# h2oiq_v4.net
KiCad netlist of a schematic drawn in EAGLE
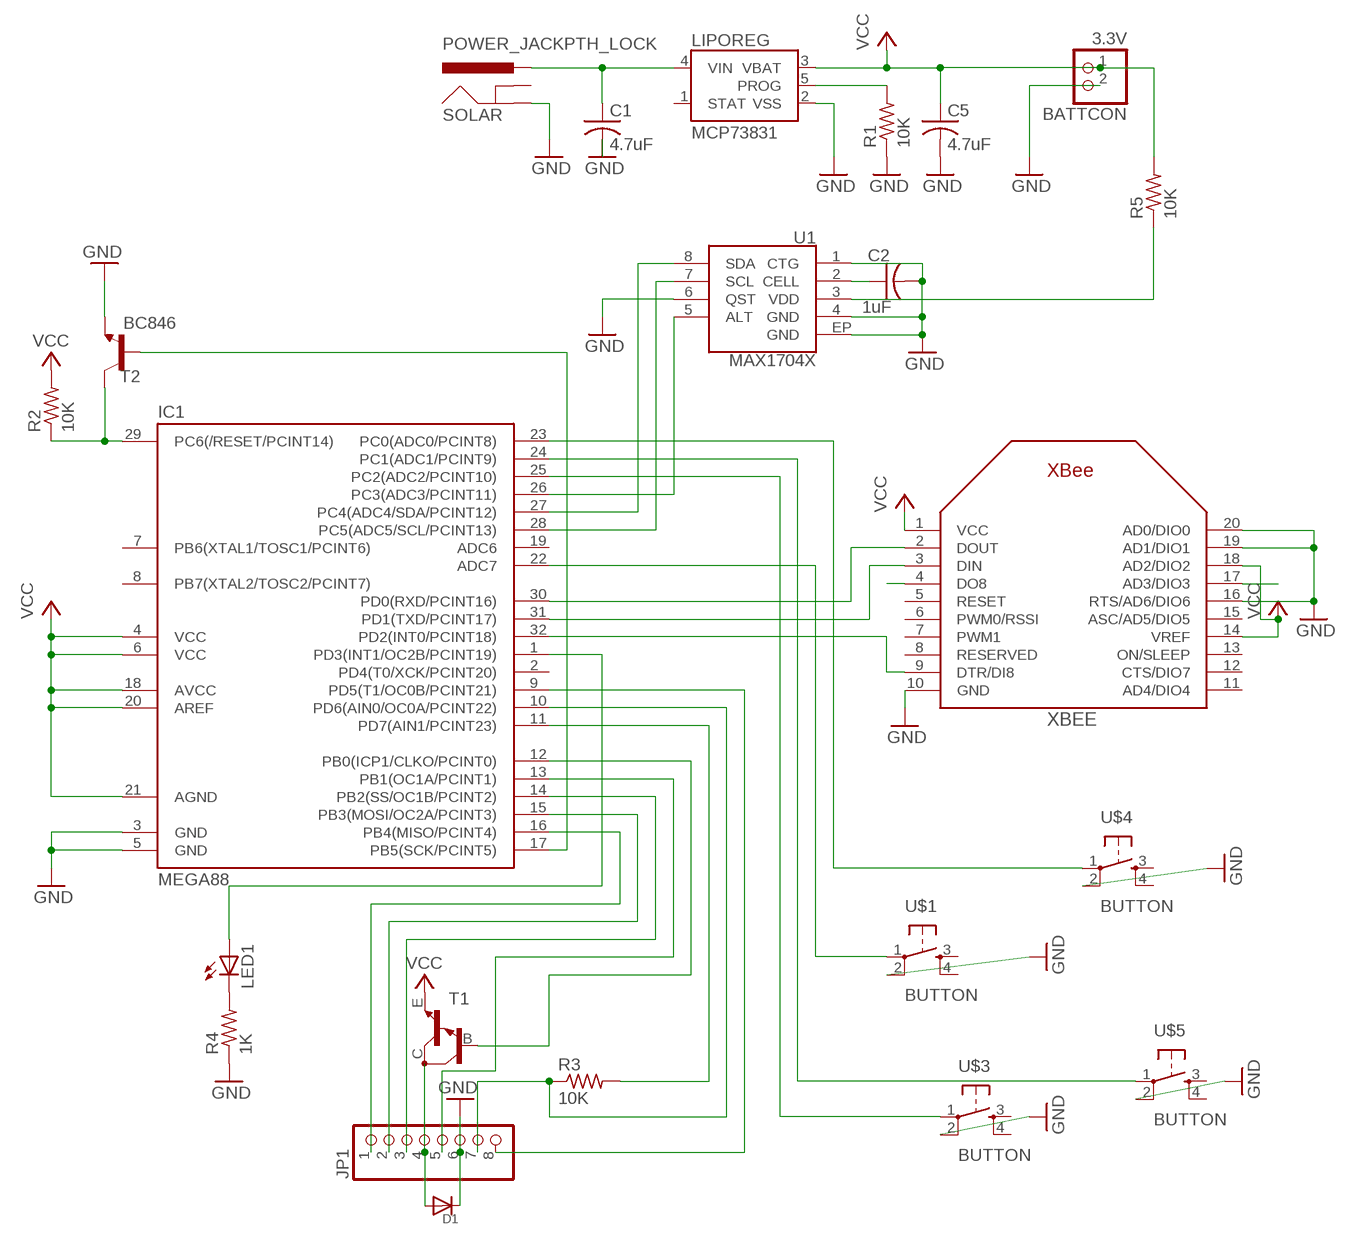
[diagram p0: schematic, sheet 1]

(export (version "E")
  (design (tool "Eeschema 10.0.6"))
  (components
    (comp (ref "BATTCON")
      (value "3.3V")
      (footprint "eagle-import:JST-PH-2-SMT")
      (libsource (lib "eagle-import") (part "JST_2PIN-SMT"))
    )
    (comp (ref "C1")
      (value "4.7uF")
      (footprint "eagle-import:C0603K")
      (libsource (lib "eagle-import") (part "C-USC0603K"))
    )
    (comp (ref "C2")
      (value "1uF")
      (footprint "eagle-import:C0603K")
      (libsource (lib "eagle-import") (part "C-USC0603K"))
    )
    (comp (ref "C5")
      (value "4.7uF")
      (footprint "eagle-import:C0603K")
      (libsource (lib "eagle-import") (part "C-USC0603K"))
    )
    (comp (ref "D1")
      (value "DIODESMA")
      (footprint "eagle-import:SMADIODE")
      (libsource (lib "eagle-import") (part "DIODESMA"))
    )
    (comp (ref "IC1")
      (value "MEGA88")
      (footprint "eagle-import:MLF32")
      (libsource (lib "eagle-import") (part "MEGA48/88/168-MU"))
    )
    (comp (ref "JP1")
      (value "PINHD-1X8LOCK")
      (footprint "eagle-import:1X08-LOCK")
      (libsource (lib "eagle-import") (part "PINHD-1X8LOCK"))
    )
    (comp (ref "LED1")
      (value "LED")
      (footprint "eagle-import:SMARTLED-TTW")
      (libsource (lib "eagle-import") (part "LED"))
    )
    (comp (ref "LIPOREG")
      (value "MCP73831")
      (footprint "eagle-import:SOT23-5")
      (libsource (lib "eagle-import") (part "MCP73831"))
    )
    (comp (ref "R1")
      (value "10K")
      (footprint "eagle-import:R0603")
      (libsource (lib "eagle-import") (part "resistor_R-US_R0603"))
    )
    (comp (ref "R2")
      (value "10K")
      (footprint "eagle-import:R0603")
      (libsource (lib "eagle-import") (part "resistor_R-US_R0603"))
    )
    (comp (ref "R3")
      (value "10K")
      (footprint "eagle-import:R0603")
      (libsource (lib "eagle-import") (part "resistor_R-US_R0603"))
    )
    (comp (ref "R4")
      (value "1K")
      (footprint "eagle-import:R0603@1")
      (libsource (lib "eagle-import") (part "R-US_R0603"))
    )
    (comp (ref "R5")
      (value "10K")
      (footprint "eagle-import:R0603@1")
      (libsource (lib "eagle-import") (part "R-US_R0603"))
    )
    (comp (ref "SOLAR")
      (value "POWER_JACKPTH_LOCK")
      (footprint "eagle-import:POWER_JACK_PTH_LOCK")
      (libsource (lib "eagle-import") (part "POWER_JACKPTH_LOCK"))
    )
    (comp (ref "T1")
      (value "MMBTA13LT1-NPN_DARL-SOT23-BEC")
      (footprint "eagle-import:SOT23-BEC")
      (libsource (lib "eagle-import") (part "-NPN_DARL-SOT23-BECMMBTA13LT1"))
    )
    (comp (ref "T2")
      (value "BC846")
      (footprint "eagle-import:SOT23")
      (libsource (lib "eagle-import") (part "BC846"))
    )
    (comp (ref "U$1")
      (value "BUTTON")
      (footprint "eagle-import:TACTILE_SWITCH_SMD")
      (libsource (lib "eagle-import") (part "TAC_SWITCHSMD"))
    )
    (comp (ref "U$3")
      (value "BUTTON")
      (footprint "eagle-import:TACTILE_SWITCH_SMD")
      (libsource (lib "eagle-import") (part "TAC_SWITCHSMD"))
    )
    (comp (ref "U$4")
      (value "BUTTON")
      (footprint "eagle-import:TACTILE_SWITCH_SMD")
      (libsource (lib "eagle-import") (part "TAC_SWITCHSMD"))
    )
    (comp (ref "U$5")
      (value "BUTTON")
      (footprint "eagle-import:TACTILE_SWITCH_SMD")
      (libsource (lib "eagle-import") (part "TAC_SWITCHSMD"))
    )
    (comp (ref "U1")
      (value "MAX1704X")
      (footprint "eagle-import:TDFN-8")
      (libsource (lib "eagle-import") (part "MAX1704X"))
    )
    (comp (ref "XBEE")
      (value "XBEE")
      (footprint "eagle-import:XBEE")
      (libsource (lib "eagle-import") (part "XBEE"))
    )
  )
  (nets
    (net (code "1") (name "/MAX1704VDD") (class "Default")
      (node (ref "R5") (pin "1") (pinfunction "1_1") (pintype "passive"))
      (node (ref "U1") (pin "3") (pinfunction "VDD_3") (pintype "bidirectional"))
      (node (ref "XBEE") (pin "4") (pinfunction "DO8_4") (pintype "output"))
    )
    (net (code "2") (name "/SERVOACT") (class "Default")
      (node (ref "D1") (pin "A") (pinfunction "A_A") (pintype "passive"))
      (node (ref "JP1") (pin "4") (pinfunction "4_4") (pintype "passive"))
      (node (ref "T1") (pin "C") (pinfunction "C_C") (pintype "passive"))
      (node (ref "XBEE") (pin "17") (pinfunction "AD3/DIO3_17") (pintype "bidirectional"))
    )
    (net (code "3") (name "GND") (class "Default")
      (node (ref "BATTCON") (pin "2") (pinfunction "1_2") (pintype "passive"))
      (node (ref "C1") (pin "2") (pinfunction "2_2") (pintype "passive"))
      (node (ref "C2") (pin "2") (pinfunction "2_2") (pintype "passive"))
      (node (ref "C5") (pin "2") (pinfunction "2_2") (pintype "passive"))
      (node (ref "D1") (pin "C") (pinfunction "C_C") (pintype "passive"))
      (node (ref "IC1") (pin "3") (pinfunction "GND_3") (pintype "power_in"))
      (node (ref "IC1") (pin "5") (pinfunction "GND_5") (pintype "power_in"))
      (node (ref "JP1") (pin "6") (pinfunction "6_6") (pintype "passive"))
      (node (ref "LIPOREG") (pin "2") (pinfunction "VSS_2") (pintype "power_in"))
      (node (ref "R1") (pin "1") (pinfunction "1_1") (pintype "passive"))
      (node (ref "R4") (pin "1") (pinfunction "1_1") (pintype "passive"))
      (node (ref "SOLAR") (pin "GND") (pinfunction "GND_GND") (pintype "bidirectional"))
      (node (ref "T2") (pin "2") (pinfunction "E_2") (pintype "passive"))
      (node (ref "U$1") (pin "2") (pinfunction "2_2") (pintype "passive"))
      (node (ref "U$3") (pin "2") (pinfunction "2_2") (pintype "passive"))
      (node (ref "U$4") (pin "2") (pinfunction "2_2") (pintype "passive"))
      (node (ref "U$5") (pin "2") (pinfunction "2_2") (pintype "passive"))
      (node (ref "U1") (pin "1") (pinfunction "CTG_1") (pintype "bidirectional"))
      (node (ref "U1") (pin "4") (pinfunction "GND_4") (pintype "bidirectional"))
      (node (ref "U1") (pin "6") (pinfunction "QST_6") (pintype "bidirectional"))
      (node (ref "U1") (pin "EP") (pinfunction "GND_EP") (pintype "bidirectional"))
      (node (ref "XBEE") (pin "10") (pinfunction "GND_10") (pintype "power_in"))
      (node (ref "XBEE") (pin "16") (pinfunction "RTS/AD6/DIO6_16") (pintype "bidirectional"))
      (node (ref "XBEE") (pin "19") (pinfunction "AD1/DIO1_19") (pintype "bidirectional"))
      (node (ref "XBEE") (pin "20") (pinfunction "AD0/DIO0_20") (pintype "bidirectional"))
    )
    (net (code "4") (name "Net-(IC1-ADC7)") (class "Default")
      (node (ref "IC1") (pin "22") (pinfunction "ADC7_22") (pintype "passive"))
      (node (ref "U$1") (pin "1") (pinfunction "1_1") (pintype "passive"))
    )
    (net (code "5") (name "Net-(IC1-PB0(ICP1{slash}CLKO{slash}PCINT0))") (class "Default")
      (node (ref "IC1") (pin "12") (pinfunction "PB0(ICP1/CLKO/PCINT0)_12") (pintype "bidirectional"))
      (node (ref "T1") (pin "B") (pinfunction "B_B") (pintype "passive"))
    )
    (net (code "6") (name "Net-(IC1-PB1(OC1A{slash}PCINT1))") (class "Default")
      (node (ref "IC1") (pin "13") (pinfunction "PB1(OC1A/PCINT1)_13") (pintype "bidirectional"))
      (node (ref "JP1") (pin "5") (pinfunction "5_5") (pintype "passive"))
    )
    (net (code "7") (name "Net-(IC1-PB2(SS{slash}OC1B{slash}PCINT2))") (class "Default")
      (node (ref "IC1") (pin "14") (pinfunction "PB2(SS/OC1B/PCINT2)_14") (pintype "bidirectional"))
      (node (ref "JP1") (pin "3") (pinfunction "3_3") (pintype "passive"))
    )
    (net (code "8") (name "Net-(IC1-PB3(MOSI{slash}OC2A{slash}PCINT3))") (class "Default")
      (node (ref "IC1") (pin "15") (pinfunction "PB3(MOSI/OC2A/PCINT3)_15") (pintype "bidirectional"))
      (node (ref "JP1") (pin "2") (pinfunction "2_2") (pintype "passive"))
    )
    (net (code "9") (name "Net-(IC1-PB4(MISO{slash}PCINT4))") (class "Default")
      (node (ref "IC1") (pin "16") (pinfunction "PB4(MISO/PCINT4)_16") (pintype "bidirectional"))
      (node (ref "JP1") (pin "1") (pinfunction "1_1") (pintype "passive"))
    )
    (net (code "10") (name "Net-(IC1-PB5(SCK{slash}PCINT5))") (class "Default")
      (node (ref "IC1") (pin "17") (pinfunction "PB5(SCK/PCINT5)_17") (pintype "bidirectional"))
      (node (ref "T2") (pin "1") (pinfunction "B_1") (pintype "passive"))
    )
    (net (code "11") (name "Net-(IC1-PC0(ADC0{slash}PCINT8))") (class "Default")
      (node (ref "IC1") (pin "23") (pinfunction "PC0(ADC0/PCINT8)_23") (pintype "bidirectional"))
      (node (ref "U$4") (pin "1") (pinfunction "1_1") (pintype "passive"))
    )
    (net (code "12") (name "Net-(IC1-PC1(ADC1{slash}PCINT9))") (class "Default")
      (node (ref "IC1") (pin "24") (pinfunction "PC1(ADC1/PCINT9)_24") (pintype "bidirectional"))
      (node (ref "U$5") (pin "1") (pinfunction "1_1") (pintype "passive"))
    )
    (net (code "13") (name "Net-(IC1-PC2(ADC2{slash}PCINT10))") (class "Default")
      (node (ref "IC1") (pin "25") (pinfunction "PC2(ADC2/PCINT10)_25") (pintype "bidirectional"))
      (node (ref "U$3") (pin "1") (pinfunction "1_1") (pintype "passive"))
    )
    (net (code "14") (name "Net-(IC1-PC3(ADC3{slash}PCINT11))") (class "Default")
      (node (ref "IC1") (pin "26") (pinfunction "PC3(ADC3/PCINT11)_26") (pintype "bidirectional"))
      (node (ref "U1") (pin "5") (pinfunction "ALT_5") (pintype "bidirectional"))
    )
    (net (code "15") (name "Net-(IC1-PC4(ADC4{slash}SDA{slash}PCINT12))") (class "Default")
      (node (ref "IC1") (pin "27") (pinfunction "PC4(ADC4/SDA/PCINT12)_27") (pintype "bidirectional"))
      (node (ref "U1") (pin "8") (pinfunction "SDA_8") (pintype "bidirectional"))
    )
    (net (code "16") (name "Net-(IC1-PC5(ADC5{slash}SCL{slash}PCINT13))") (class "Default")
      (node (ref "IC1") (pin "28") (pinfunction "PC5(ADC5/SCL/PCINT13)_28") (pintype "bidirectional"))
      (node (ref "U1") (pin "7") (pinfunction "SCL_7") (pintype "bidirectional"))
    )
    (net (code "17") (name "Net-(IC1-PC6({slash}RESET{slash}PCINT14))") (class "Default")
      (node (ref "IC1") (pin "29") (pinfunction "PC6(/RESET/PCINT14)_29") (pintype "bidirectional"))
      (node (ref "R2") (pin "1") (pinfunction "1_1") (pintype "passive"))
      (node (ref "T2") (pin "3") (pinfunction "C_3") (pintype "passive"))
    )
    (net (code "18") (name "Net-(IC1-PD0(RXD{slash}PCINT16))") (class "Default")
      (node (ref "IC1") (pin "30") (pinfunction "PD0(RXD/PCINT16)_30") (pintype "bidirectional"))
      (node (ref "XBEE") (pin "2") (pinfunction "DOUT_2") (pintype "output"))
    )
    (net (code "19") (name "Net-(IC1-PD1(TXD{slash}PCINT17))") (class "Default")
      (node (ref "IC1") (pin "31") (pinfunction "PD1(TXD/PCINT17)_31") (pintype "bidirectional"))
      (node (ref "XBEE") (pin "3") (pinfunction "DIN_3") (pintype "input"))
    )
    (net (code "20") (name "Net-(IC1-PD2(INT0{slash}PCINT18))") (class "Default")
      (node (ref "IC1") (pin "32") (pinfunction "PD2(INT0/PCINT18)_32") (pintype "bidirectional"))
      (node (ref "XBEE") (pin "9") (pinfunction "DTR/DI8_9") (pintype "input"))
    )
    (net (code "21") (name "Net-(IC1-PD3(INT1{slash}OC2B{slash}PCINT19))") (class "Default")
      (node (ref "IC1") (pin "1") (pinfunction "PD3(INT1/OC2B/PCINT19)_1") (pintype "bidirectional"))
      (node (ref "LED1") (pin "A@1") (pinfunction "A_A@1") (pintype "passive"))
    )
    (net (code "22") (name "Net-(IC1-PD5(T1{slash}OC0B{slash}PCINT21))") (class "Default")
      (node (ref "IC1") (pin "9") (pinfunction "PD5(T1/OC0B/PCINT21)_9") (pintype "bidirectional"))
      (node (ref "JP1") (pin "8") (pinfunction "8_8") (pintype "passive"))
    )
    (net (code "23") (name "Net-(IC1-PD6(AIN0{slash}OC0A{slash}PCINT22))") (class "Default")
      (node (ref "IC1") (pin "10") (pinfunction "PD6(AIN0/OC0A/PCINT22)_10") (pintype "bidirectional"))
      (node (ref "JP1") (pin "7") (pinfunction "7_7") (pintype "passive"))
      (node (ref "R3") (pin "1") (pinfunction "1_1") (pintype "passive"))
    )
    (net (code "24") (name "Net-(IC1-PD7(AIN1{slash}PCINT23))") (class "Default")
      (node (ref "IC1") (pin "11") (pinfunction "PD7(AIN1/PCINT23)_11") (pintype "bidirectional"))
      (node (ref "R3") (pin "2") (pinfunction "2_2") (pintype "passive"))
    )
    (net (code "25") (name "Net-(LED1-C)") (class "Default")
      (node (ref "LED1") (pin "C@1") (pinfunction "C_C@1") (pintype "passive"))
      (node (ref "R4") (pin "2") (pinfunction "2_2") (pintype "passive"))
    )
    (net (code "26") (name "Net-(LIPOREG-PROG)") (class "Default")
      (node (ref "LIPOREG") (pin "5") (pinfunction "PROG_5") (pintype "input"))
      (node (ref "R1") (pin "2") (pinfunction "2_2") (pintype "passive"))
    )
    (net (code "27") (name "Net-(LIPOREG-VIN)") (class "Default")
      (node (ref "C1") (pin "1") (pinfunction "1_1") (pintype "passive"))
      (node (ref "LIPOREG") (pin "4") (pinfunction "VIN_4") (pintype "power_in"))
      (node (ref "SOLAR") (pin "PWR") (pinfunction "PWR_PWR") (pintype "bidirectional"))
    )
    (net (code "28") (name "Net-(U1-CELL)") (class "Default")
      (node (ref "C2") (pin "1") (pinfunction "1_1") (pintype "passive"))
      (node (ref "U1") (pin "2") (pinfunction "CELL_2") (pintype "bidirectional"))
    )
    (net (code "29") (name "VCC") (class "Default")
      (node (ref "BATTCON") (pin "1") (pinfunction "2_1") (pintype "passive"))
      (node (ref "C5") (pin "1") (pinfunction "1_1") (pintype "passive"))
      (node (ref "IC1") (pin "18") (pinfunction "AVCC_18") (pintype "passive"))
      (node (ref "IC1") (pin "20") (pinfunction "AREF_20") (pintype "passive"))
      (node (ref "IC1") (pin "21") (pinfunction "AGND_21") (pintype "power_in"))
      (node (ref "IC1") (pin "4") (pinfunction "VCC_4") (pintype "power_in"))
      (node (ref "IC1") (pin "6") (pinfunction "VCC_6") (pintype "power_in"))
      (node (ref "LIPOREG") (pin "3") (pinfunction "VBAT_3") (pintype "power_in"))
      (node (ref "R2") (pin "2") (pinfunction "2_2") (pintype "passive"))
      (node (ref "R5") (pin "2") (pinfunction "2_2") (pintype "passive"))
      (node (ref "T1") (pin "E") (pinfunction "E_E") (pintype "passive"))
      (node (ref "XBEE") (pin "1") (pinfunction "VCC_1") (pintype "power_in"))
      (node (ref "XBEE") (pin "14") (pinfunction "VREF_14") (pintype "input"))
      (node (ref "XBEE") (pin "18") (pinfunction "AD2/DIO2_18") (pintype "bidirectional"))
    )
    (net (code "30") (name "unconnected-(IC1-ADC6-Pad19)") (class "Default")
      (node (ref "IC1") (pin "19") (pinfunction "ADC6_19") (pintype "passive"))
    )
    (net (code "31") (name "unconnected-(IC1-PB6(XTAL1{slash}TOSC1{slash}PCINT6)-Pad7)") (class "Default")
      (node (ref "IC1") (pin "7") (pinfunction "PB6(XTAL1/TOSC1/PCINT6)_7") (pintype "bidirectional"))
    )
    (net (code "32") (name "unconnected-(IC1-PB7(XTAL2{slash}TOSC2{slash}PCINT7)-Pad8)") (class "Default")
      (node (ref "IC1") (pin "8") (pinfunction "PB7(XTAL2/TOSC2/PCINT7)_8") (pintype "bidirectional"))
    )
    (net (code "33") (name "unconnected-(IC1-PD4(T0{slash}XCK{slash}PCINT20)-Pad2)") (class "Default")
      (node (ref "IC1") (pin "2") (pinfunction "PD4(T0/XCK/PCINT20)_2") (pintype "bidirectional"))
    )
    (net (code "34") (name "unconnected-(LIPOREG-STAT-Pad1)") (class "Default")
      (node (ref "LIPOREG") (pin "1") (pinfunction "STAT_1") (pintype "output"))
    )
    (net (code "35") (name "unconnected-(SOLAR-PadGNDBREAK)") (class "Default")
      (node (ref "SOLAR") (pin "GNDBREAK") (pinfunction "GNDBREAK_GNDBREAK") (pintype "bidirectional"))
    )
    (net (code "36") (name "unconnected-(U$1-Pad3)") (class "Default")
      (node (ref "U$1") (pin "3") (pinfunction "3_3") (pintype "passive"))
    )
    (net (code "37") (name "unconnected-(U$1-Pad4)") (class "Default")
      (node (ref "U$1") (pin "4") (pinfunction "4_4") (pintype "passive"))
    )
    (net (code "38") (name "unconnected-(U$3-Pad3)") (class "Default")
      (node (ref "U$3") (pin "3") (pinfunction "3_3") (pintype "passive"))
    )
    (net (code "39") (name "unconnected-(U$3-Pad4)") (class "Default")
      (node (ref "U$3") (pin "4") (pinfunction "4_4") (pintype "passive"))
    )
    (net (code "40") (name "unconnected-(U$4-Pad3)") (class "Default")
      (node (ref "U$4") (pin "3") (pinfunction "3_3") (pintype "passive"))
    )
    (net (code "41") (name "unconnected-(U$4-Pad4)") (class "Default")
      (node (ref "U$4") (pin "4") (pinfunction "4_4") (pintype "passive"))
    )
    (net (code "42") (name "unconnected-(U$5-Pad3)") (class "Default")
      (node (ref "U$5") (pin "3") (pinfunction "3_3") (pintype "passive"))
    )
    (net (code "43") (name "unconnected-(U$5-Pad4)") (class "Default")
      (node (ref "U$5") (pin "4") (pinfunction "4_4") (pintype "passive"))
    )
    (net (code "44") (name "unconnected-(XBEE-AD4{slash}DIO4-Pad11)") (class "Default")
      (node (ref "XBEE") (pin "11") (pinfunction "AD4/DIO4_11") (pintype "bidirectional"))
    )
    (net (code "45") (name "unconnected-(XBEE-ASC{slash}AD5{slash}DIO5-Pad15)") (class "Default")
      (node (ref "XBEE") (pin "15") (pinfunction "ASC/AD5/DIO5_15") (pintype "bidirectional"))
    )
    (net (code "46") (name "unconnected-(XBEE-CTS{slash}DIO7-Pad12)") (class "Default")
      (node (ref "XBEE") (pin "12") (pinfunction "CTS/DIO7_12") (pintype "bidirectional"))
    )
    (net (code "47") (name "unconnected-(XBEE-ON{slash}SLEEP-Pad13)") (class "Default")
      (node (ref "XBEE") (pin "13") (pinfunction "ON/SLEEP_13") (pintype "output"))
    )
    (net (code "48") (name "unconnected-(XBEE-PWM0{slash}RSSI-Pad6)") (class "Default")
      (node (ref "XBEE") (pin "6") (pinfunction "PWM0/RSSI_6") (pintype "output"))
    )
    (net (code "49") (name "unconnected-(XBEE-PWM1-Pad7)") (class "Default")
      (node (ref "XBEE") (pin "7") (pinfunction "PWM1_7") (pintype "output"))
    )
    (net (code "50") (name "unconnected-(XBEE-RESERVED-Pad8)") (class "Default")
      (node (ref "XBEE") (pin "8") (pinfunction "RESERVED_8") (pintype "no_connect"))
    )
    (net (code "51") (name "unconnected-(XBEE-RESET-Pad5)") (class "Default")
      (node (ref "XBEE") (pin "5") (pinfunction "RESET_5") (pintype "input"))
    )
  )
)
